# MainBoard_v7_1_3.net
KiCad netlist of a schematic drawn in EAGLE
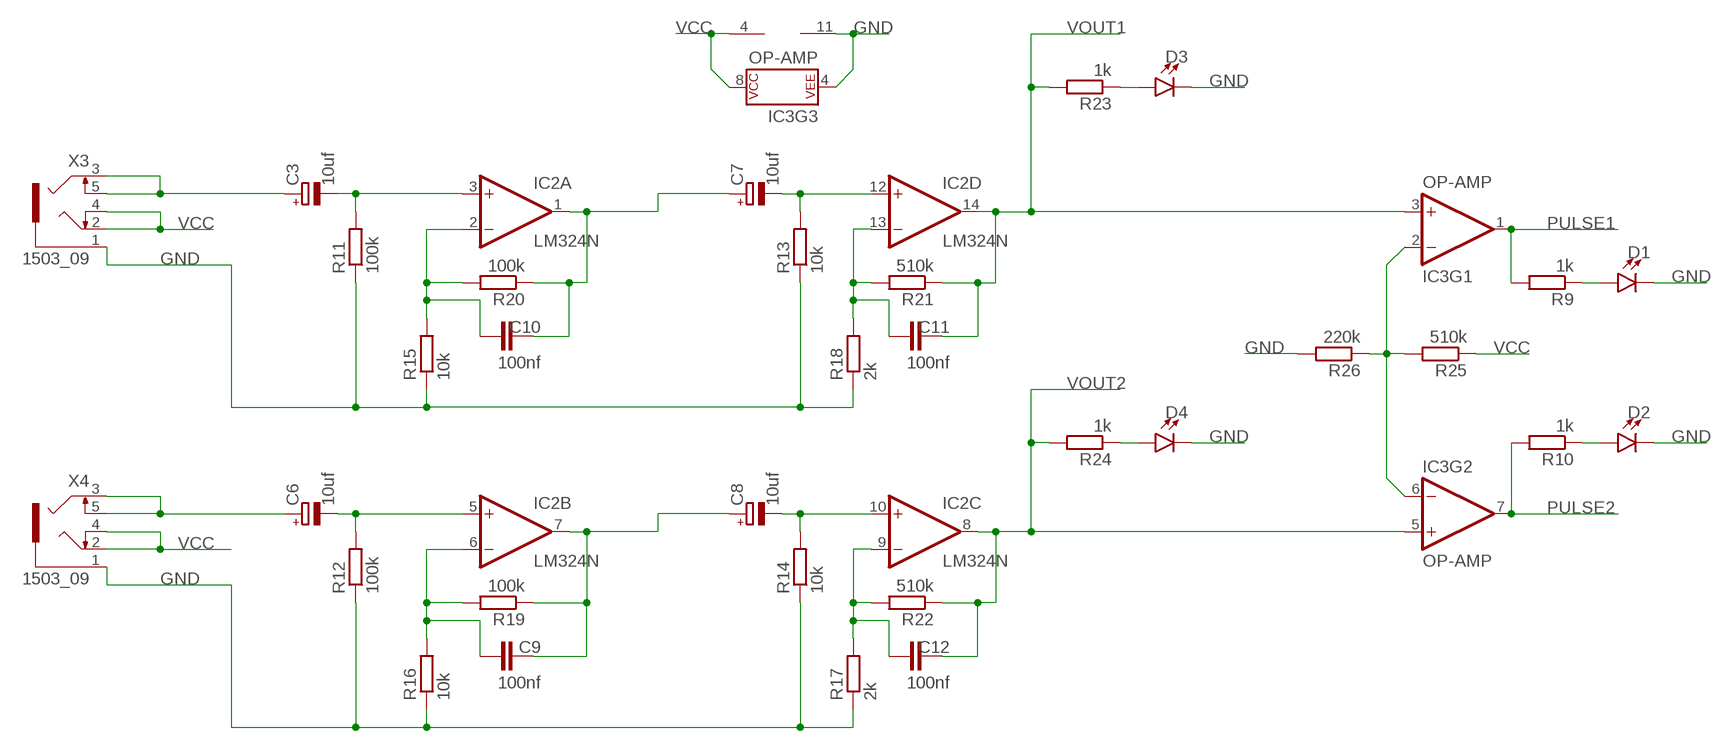
[diagram p0: schematic, sheet 1]
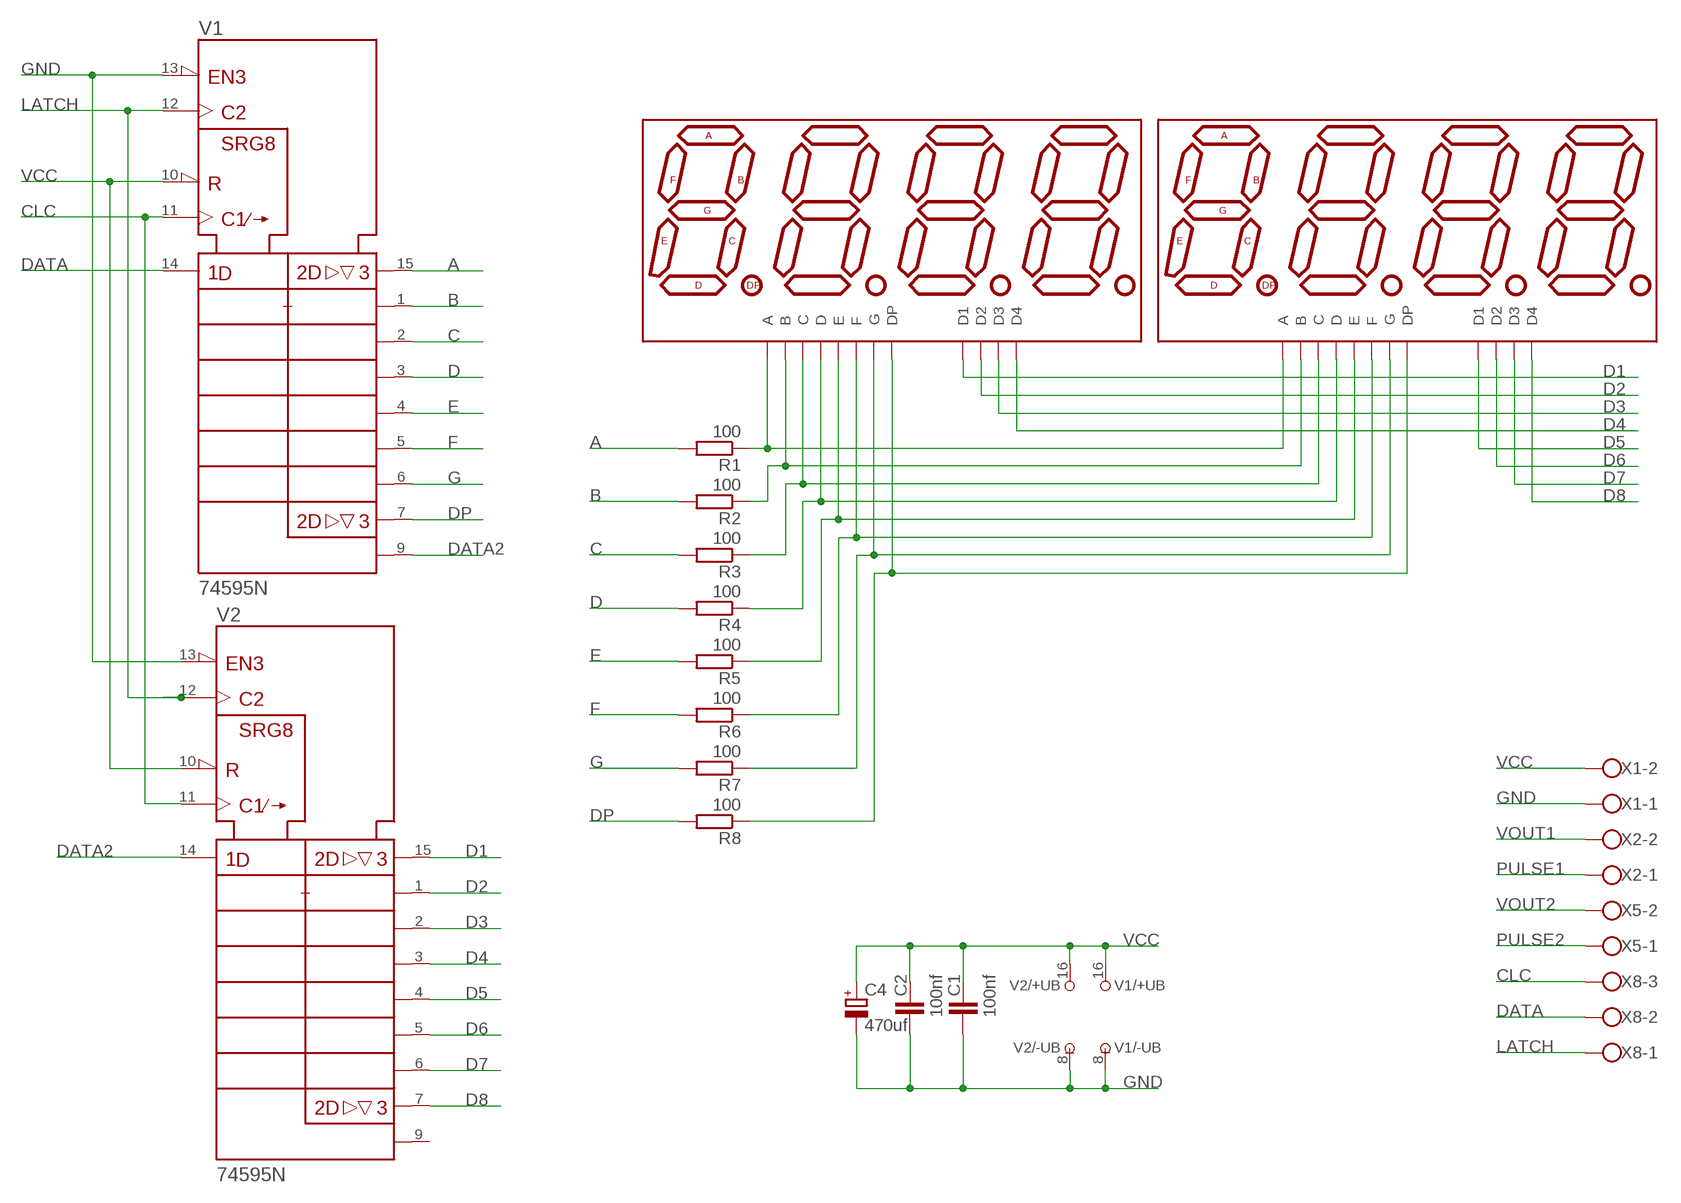
[diagram p1: schematic, sheet 2]

(export (version "E")
  (design (tool "Eeschema 10.0.6"))
  (components
    (comp (ref "C3")
      (value "10uf")
      (footprint "eagle-import:E2-5")
      (libsource (lib "eagle-import") (part "CPOL-EUE2-5"))
    )
    (comp (ref "C6")
      (value "10uf")
      (footprint "eagle-import:E2-5")
      (libsource (lib "eagle-import") (part "CPOL-EUE2-5"))
    )
    (comp (ref "C7")
      (value "10uf")
      (footprint "eagle-import:E2-5")
      (libsource (lib "eagle-import") (part "CPOL-EUE2-5"))
    )
    (comp (ref "C8")
      (value "10uf")
      (footprint "eagle-import:E2-5")
      (libsource (lib "eagle-import") (part "CPOL-EUE2-5"))
    )
    (comp (ref "C9")
      (value "100nf")
      (footprint "eagle-import:C050-030X075")
      (libsource (lib "eagle-import") (part "C-EU050-030X075"))
    )
    (comp (ref "C10")
      (value "100nf")
      (footprint "eagle-import:C050-030X075")
      (libsource (lib "eagle-import") (part "C-EU050-030X075"))
    )
    (comp (ref "C11")
      (value "100nf")
      (footprint "eagle-import:C050-030X075")
      (libsource (lib "eagle-import") (part "C-EU050-030X075"))
    )
    (comp (ref "C12")
      (value "100nf")
      (footprint "eagle-import:C050-030X075")
      (libsource (lib "eagle-import") (part "C-EU050-030X075"))
    )
    (comp (ref "D1")
      (value "LED5MM")
      (footprint "eagle-import:LED_5MM")
      (libsource (lib "eagle-import") (part "LED5MM"))
    )
    (comp (ref "D2")
      (value "LED5MM")
      (footprint "eagle-import:LED_5MM")
      (libsource (lib "eagle-import") (part "LED5MM"))
    )
    (comp (ref "D3")
      (value "LED5MM")
      (footprint "eagle-import:LED_5MM")
      (libsource (lib "eagle-import") (part "LED5MM"))
    )
    (comp (ref "D4")
      (value "LED5MM")
      (footprint "eagle-import:LED_5MM")
      (libsource (lib "eagle-import") (part "LED5MM"))
    )
    (comp (ref "IC2")
      (value "LM324N")
      (footprint "eagle-import:DIL14")
      (libsource (lib "eagle-import") (part "LM324N"))
    )
    (comp (ref "IC3")
      (value "OP-AMP")
      (footprint "eagle-import:DIP08")
      (libsource (lib "eagle-import") (part "OPAMP-DUALDIP"))
    )
    (comp (ref "R9")
      (value "1k")
      (footprint "eagle-import:0207_10")
      (libsource (lib "eagle-import") (part "R-EU_0207/10"))
    )
    (comp (ref "R10")
      (value "1k")
      (footprint "eagle-import:0207_10")
      (libsource (lib "eagle-import") (part "R-EU_0207/10"))
    )
    (comp (ref "R11")
      (value "100k")
      (footprint "eagle-import:0207_10")
      (libsource (lib "eagle-import") (part "R-EU_0207/10"))
    )
    (comp (ref "R12")
      (value "100k")
      (footprint "eagle-import:0207_10")
      (libsource (lib "eagle-import") (part "R-EU_0207/10"))
    )
    (comp (ref "R13")
      (value "10k")
      (footprint "eagle-import:0207_10")
      (libsource (lib "eagle-import") (part "R-EU_0207/10"))
    )
    (comp (ref "R14")
      (value "10k")
      (footprint "eagle-import:0207_10")
      (libsource (lib "eagle-import") (part "R-EU_0207/10"))
    )
    (comp (ref "R15")
      (value "10k")
      (footprint "eagle-import:0207_10")
      (libsource (lib "eagle-import") (part "R-EU_0207/10"))
    )
    (comp (ref "R16")
      (value "10k")
      (footprint "eagle-import:0207_10")
      (libsource (lib "eagle-import") (part "R-EU_0207/10"))
    )
    (comp (ref "R17")
      (value "2k")
      (footprint "eagle-import:0207_10")
      (libsource (lib "eagle-import") (part "R-EU_0207/10"))
    )
    (comp (ref "R18")
      (value "2k")
      (footprint "eagle-import:0207_10")
      (libsource (lib "eagle-import") (part "R-EU_0207/10"))
    )
    (comp (ref "R19")
      (value "100k")
      (footprint "eagle-import:0207_10")
      (libsource (lib "eagle-import") (part "R-EU_0207/10"))
    )
    (comp (ref "R20")
      (value "100k")
      (footprint "eagle-import:0207_10")
      (libsource (lib "eagle-import") (part "R-EU_0207/10"))
    )
    (comp (ref "R21")
      (value "510k")
      (footprint "eagle-import:0207_10")
      (libsource (lib "eagle-import") (part "R-EU_0207/10"))
    )
    (comp (ref "R22")
      (value "510k")
      (footprint "eagle-import:0207_10")
      (libsource (lib "eagle-import") (part "R-EU_0207/10"))
    )
    (comp (ref "R23")
      (value "1k")
      (footprint "eagle-import:0207_10")
      (libsource (lib "eagle-import") (part "R-EU_0207/10"))
    )
    (comp (ref "R24")
      (value "1k")
      (footprint "eagle-import:0207_10")
      (libsource (lib "eagle-import") (part "R-EU_0207/10"))
    )
    (comp (ref "R25")
      (value "510k")
      (footprint "eagle-import:0207_10")
      (libsource (lib "eagle-import") (part "R-EU_0207/10"))
    )
    (comp (ref "R26")
      (value "220k")
      (footprint "eagle-import:0207_10")
      (libsource (lib "eagle-import") (part "R-EU_0207/10"))
    )
    (comp (ref "X3")
      (value "1503_09")
      (footprint "eagle-import:1503_09")
      (libsource (lib "eagle-import") (part "1503_09"))
    )
    (comp (ref "X4")
      (value "1503_09")
      (footprint "eagle-import:1503_09")
      (libsource (lib "eagle-import") (part "1503_09"))
    )
    (comp (ref "C1")
      (value "100nf")
      (footprint "eagle-import:C050-030X075")
      (libsource (lib "eagle-import") (part "C-EU050-030X075"))
    )
    (comp (ref "C2")
      (value "100nf")
      (footprint "eagle-import:C050-030X075")
      (libsource (lib "eagle-import") (part "C-EU050-030X075"))
    )
    (comp (ref "C4")
      (value "470uf")
      (footprint "eagle-import:E3,5-8")
      (libsource (lib "eagle-import") (part "CPOL-EUE3.5-8"))
    )
    (comp (ref "DISP1")
      (value "ATA8041AB")
      (footprint "eagle-import:7-SEGMENT-4DIGIT-20MM")
      (libsource (lib "eagle-import") (part "7-SEGMENT-4DIGIT-20MM-BLUE"))
    )
    (comp (ref "DISP2")
      (value "ATA8041AB")
      (footprint "eagle-import:7-SEGMENT-4DIGIT-20MM")
      (libsource (lib "eagle-import") (part "7-SEGMENT-4DIGIT-20MM-BLUE"))
    )
    (comp (ref "R1")
      (value "100")
      (footprint "eagle-import:0207_10")
      (libsource (lib "eagle-import") (part "R-EU_0207/10"))
    )
    (comp (ref "R2")
      (value "100")
      (footprint "eagle-import:0207_10")
      (libsource (lib "eagle-import") (part "R-EU_0207/10"))
    )
    (comp (ref "R3")
      (value "100")
      (footprint "eagle-import:0207_10")
      (libsource (lib "eagle-import") (part "R-EU_0207/10"))
    )
    (comp (ref "R4")
      (value "100")
      (footprint "eagle-import:0207_10")
      (libsource (lib "eagle-import") (part "R-EU_0207/10"))
    )
    (comp (ref "R5")
      (value "100")
      (footprint "eagle-import:0207_10")
      (libsource (lib "eagle-import") (part "R-EU_0207/10"))
    )
    (comp (ref "R6")
      (value "100")
      (footprint "eagle-import:0207_10")
      (libsource (lib "eagle-import") (part "R-EU_0207/10"))
    )
    (comp (ref "R7")
      (value "100")
      (footprint "eagle-import:0207_10")
      (libsource (lib "eagle-import") (part "R-EU_0207/10"))
    )
    (comp (ref "R8")
      (value "100")
      (footprint "eagle-import:0207_10")
      (libsource (lib "eagle-import") (part "R-EU_0207/10"))
    )
    (comp (ref "V1")
      (value "74595N")
      (footprint "eagle-import:DIL16")
      (libsource (lib "eagle-import") (part "74595N"))
    )
    (comp (ref "V2")
      (value "74595N")
      (footprint "eagle-import:DIL16")
      (libsource (lib "eagle-import") (part "74595N"))
    )
    (comp (ref "X1")
      (value "W237-102")
      (footprint "eagle-import:W237-102")
      (fields (field (name "MPN") "237-102"))
      (libsource (lib "eagle-import") (part "W237-102"))
    )
    (comp (ref "X2")
      (value "W237-102")
      (footprint "eagle-import:W237-102")
      (fields (field (name "MPN") "237-102"))
      (libsource (lib "eagle-import") (part "W237-102"))
    )
    (comp (ref "X5")
      (value "W237-102")
      (footprint "eagle-import:W237-102")
      (fields (field (name "MPN") "237-102"))
      (libsource (lib "eagle-import") (part "W237-102"))
    )
    (comp (ref "X8")
      (value "W237-103")
      (footprint "eagle-import:W237-103")
      (fields (field (name "MPN") "237-103"))
      (libsource (lib "eagle-import") (part "W237-103"))
    )
  )
  (nets
    (net (code "1") (name "A") (class "Default")
      (node (ref "R1") (pin "2") (pinfunction "2_2") (pintype "passive"))
      (node (ref "V1") (pin "15") (pinfunction "QA_15") (pintype "tri_state"))
    )
    (net (code "2") (name "B") (class "Default")
      (node (ref "R2") (pin "2") (pinfunction "2_2") (pintype "passive"))
      (node (ref "V1") (pin "1") (pinfunction "QB_1") (pintype "tri_state"))
    )
    (net (code "3") (name "C") (class "Default")
      (node (ref "R3") (pin "2") (pinfunction "2_2") (pintype "passive"))
      (node (ref "V1") (pin "2") (pinfunction "QC_2") (pintype "tri_state"))
    )
    (net (code "4") (name "CLC") (class "Default")
      (node (ref "V1") (pin "11") (pinfunction "SRCK_11") (pintype "input"))
      (node (ref "V2") (pin "11") (pinfunction "SRCK_11") (pintype "input"))
      (node (ref "X8") (pin "3") (pinfunction "KL_3") (pintype "passive"))
    )
    (net (code "5") (name "D") (class "Default")
      (node (ref "R4") (pin "2") (pinfunction "2_2") (pintype "passive"))
      (node (ref "V1") (pin "3") (pinfunction "QD_3") (pintype "tri_state"))
    )
    (net (code "6") (name "D1") (class "Default")
      (node (ref "DISP2") (pin "12") (pinfunction "D1_12") (pintype "bidirectional"))
      (node (ref "V2") (pin "15") (pinfunction "QA_15") (pintype "tri_state"))
    )
    (net (code "7") (name "D2") (class "Default")
      (node (ref "DISP2") (pin "9") (pinfunction "D2_9") (pintype "bidirectional"))
      (node (ref "V2") (pin "1") (pinfunction "QB_1") (pintype "tri_state"))
    )
    (net (code "8") (name "D3") (class "Default")
      (node (ref "DISP2") (pin "8") (pinfunction "D3_8") (pintype "bidirectional"))
      (node (ref "V2") (pin "2") (pinfunction "QC_2") (pintype "tri_state"))
    )
    (net (code "9") (name "D4") (class "Default")
      (node (ref "DISP2") (pin "6") (pinfunction "D4_6") (pintype "bidirectional"))
      (node (ref "V2") (pin "3") (pinfunction "QD_3") (pintype "tri_state"))
    )
    (net (code "10") (name "D5") (class "Default")
      (node (ref "DISP1") (pin "12") (pinfunction "D1_12") (pintype "bidirectional"))
      (node (ref "V2") (pin "4") (pinfunction "QE_4") (pintype "tri_state"))
    )
    (net (code "11") (name "D6") (class "Default")
      (node (ref "DISP1") (pin "9") (pinfunction "D2_9") (pintype "bidirectional"))
      (node (ref "V2") (pin "5") (pinfunction "QF_5") (pintype "tri_state"))
    )
    (net (code "12") (name "D7") (class "Default")
      (node (ref "DISP1") (pin "8") (pinfunction "D3_8") (pintype "bidirectional"))
      (node (ref "V2") (pin "6") (pinfunction "QG_6") (pintype "tri_state"))
    )
    (net (code "13") (name "D8") (class "Default")
      (node (ref "DISP1") (pin "6") (pinfunction "D4_6") (pintype "bidirectional"))
      (node (ref "V2") (pin "7") (pinfunction "QH_7") (pintype "tri_state"))
    )
    (net (code "14") (name "DATA") (class "Default")
      (node (ref "V1") (pin "14") (pinfunction "SER_14") (pintype "input"))
      (node (ref "X8") (pin "2") (pinfunction "KL_2") (pintype "passive"))
    )
    (net (code "15") (name "DATA2") (class "Default")
      (node (ref "V1") (pin "9") (pinfunction "QH*_9") (pintype "output"))
      (node (ref "V2") (pin "14") (pinfunction "SER_14") (pintype "input"))
    )
    (net (code "16") (name "DP") (class "Default")
      (node (ref "R8") (pin "2") (pinfunction "2_2") (pintype "passive"))
      (node (ref "V1") (pin "7") (pinfunction "QH_7") (pintype "tri_state"))
    )
    (net (code "17") (name "E") (class "Default")
      (node (ref "R5") (pin "2") (pinfunction "2_2") (pintype "passive"))
      (node (ref "V1") (pin "4") (pinfunction "QE_4") (pintype "tri_state"))
    )
    (net (code "18") (name "F") (class "Default")
      (node (ref "R6") (pin "2") (pinfunction "2_2") (pintype "passive"))
      (node (ref "V1") (pin "5") (pinfunction "QF_5") (pintype "tri_state"))
    )
    (net (code "19") (name "G") (class "Default")
      (node (ref "R7") (pin "2") (pinfunction "2_2") (pintype "passive"))
      (node (ref "V1") (pin "6") (pinfunction "QG_6") (pintype "tri_state"))
    )
    (net (code "20") (name "GND") (class "Default")
      (node (ref "C1") (pin "1") (pinfunction "1_1") (pintype "passive"))
      (node (ref "C2") (pin "1") (pinfunction "1_1") (pintype "passive"))
      (node (ref "C4") (pin "-") (pinfunction "-_-") (pintype "passive"))
      (node (ref "D1") (pin "K") (pinfunction "C_K") (pintype "passive"))
      (node (ref "D2") (pin "K") (pinfunction "C_K") (pintype "passive"))
      (node (ref "D3") (pin "K") (pinfunction "C_K") (pintype "passive"))
      (node (ref "D4") (pin "K") (pinfunction "C_K") (pintype "passive"))
      (node (ref "IC2") (pin "11") (pinfunction "V-_11") (pintype "power_in"))
      (node (ref "IC3") (pin "4") (pinfunction "P$V-_4") (pintype "bidirectional"))
      (node (ref "R11") (pin "1") (pinfunction "1_1") (pintype "passive"))
      (node (ref "R12") (pin "1") (pinfunction "1_1") (pintype "passive"))
      (node (ref "R13") (pin "1") (pinfunction "1_1") (pintype "passive"))
      (node (ref "R14") (pin "1") (pinfunction "1_1") (pintype "passive"))
      (node (ref "R15") (pin "1") (pinfunction "1_1") (pintype "passive"))
      (node (ref "R16") (pin "1") (pinfunction "1_1") (pintype "passive"))
      (node (ref "R17") (pin "1") (pinfunction "1_1") (pintype "passive"))
      (node (ref "R18") (pin "1") (pinfunction "1_1") (pintype "passive"))
      (node (ref "R26") (pin "2") (pinfunction "2_2") (pintype "passive"))
      (node (ref "V1") (pin "13") (pinfunction "~{G}_13") (pintype "input"))
      (node (ref "V1") (pin "8") (pinfunction "-UB_8") (pintype "power_in"))
      (node (ref "V2") (pin "13") (pinfunction "~{G}_13") (pintype "input"))
      (node (ref "V2") (pin "8") (pinfunction "-UB_8") (pintype "power_in"))
      (node (ref "X1") (pin "1") (pinfunction "KL_1") (pintype "passive"))
      (node (ref "X3") (pin "1") (pinfunction "1_1") (pintype "passive"))
      (node (ref "X4") (pin "1") (pinfunction "1_1") (pintype "passive"))
    )
    (net (code "21") (name "LATCH") (class "Default")
      (node (ref "V1") (pin "12") (pinfunction "RCK_12") (pintype "input"))
      (node (ref "V2") (pin "12") (pinfunction "RCK_12") (pintype "input"))
      (node (ref "X8") (pin "1") (pinfunction "KL_1") (pintype "passive"))
    )
    (net (code "22") (name "Net-(C3-Pad+)") (class "Default")
      (node (ref "C3") (pin "+") (pinfunction "+_+") (pintype "passive"))
      (node (ref "X3") (pin "3") (pinfunction "3_3") (pintype "passive"))
      (node (ref "X3") (pin "5") (pinfunction "5_5") (pintype "passive"))
    )
    (net (code "23") (name "Net-(C6-Pad+)") (class "Default")
      (node (ref "C6") (pin "+") (pinfunction "+_+") (pintype "passive"))
      (node (ref "X4") (pin "3") (pinfunction "3_3") (pintype "passive"))
      (node (ref "X4") (pin "5") (pinfunction "5_5") (pintype "passive"))
    )
    (net (code "24") (name "Net-(D1-PadA)") (class "Default")
      (node (ref "D1") (pin "A") (pinfunction "A_A") (pintype "passive"))
      (node (ref "R9") (pin "1") (pinfunction "1_1") (pintype "passive"))
    )
    (net (code "25") (name "Net-(D2-PadA)") (class "Default")
      (node (ref "D2") (pin "A") (pinfunction "A_A") (pintype "passive"))
      (node (ref "R10") (pin "1") (pinfunction "1_1") (pintype "passive"))
    )
    (net (code "26") (name "Net-(D3-PadA)") (class "Default")
      (node (ref "D3") (pin "A") (pinfunction "A_A") (pintype "passive"))
      (node (ref "R23") (pin "1") (pinfunction "1_1") (pintype "passive"))
    )
    (net (code "27") (name "Net-(D4-PadA)") (class "Default")
      (node (ref "D4") (pin "A") (pinfunction "A_A") (pintype "passive"))
      (node (ref "R24") (pin "1") (pinfunction "1_1") (pintype "passive"))
    )
    (net (code "28") (name "Net-(DISP1-A)") (class "Default")
      (node (ref "DISP1") (pin "11") (pinfunction "A_11") (pintype "bidirectional"))
      (node (ref "DISP2") (pin "11") (pinfunction "A_11") (pintype "bidirectional"))
      (node (ref "R1") (pin "1") (pinfunction "1_1") (pintype "passive"))
    )
    (net (code "29") (name "Net-(DISP1-B)") (class "Default")
      (node (ref "DISP1") (pin "7") (pinfunction "B_7") (pintype "bidirectional"))
      (node (ref "DISP2") (pin "7") (pinfunction "B_7") (pintype "bidirectional"))
      (node (ref "R2") (pin "1") (pinfunction "1_1") (pintype "passive"))
    )
    (net (code "30") (name "Net-(DISP1-C)") (class "Default")
      (node (ref "DISP1") (pin "4") (pinfunction "C_4") (pintype "bidirectional"))
      (node (ref "DISP2") (pin "4") (pinfunction "C_4") (pintype "bidirectional"))
      (node (ref "R3") (pin "1") (pinfunction "1_1") (pintype "passive"))
    )
    (net (code "31") (name "Net-(DISP1-D)") (class "Default")
      (node (ref "DISP1") (pin "2") (pinfunction "D_2") (pintype "bidirectional"))
      (node (ref "DISP2") (pin "2") (pinfunction "D_2") (pintype "bidirectional"))
      (node (ref "R4") (pin "1") (pinfunction "1_1") (pintype "passive"))
    )
    (net (code "32") (name "Net-(DISP1-DP)") (class "Default")
      (node (ref "DISP1") (pin "3") (pinfunction "DP_3") (pintype "bidirectional"))
      (node (ref "DISP2") (pin "3") (pinfunction "DP_3") (pintype "bidirectional"))
      (node (ref "R8") (pin "1") (pinfunction "1_1") (pintype "passive"))
    )
    (net (code "33") (name "Net-(DISP1-E)") (class "Default")
      (node (ref "DISP1") (pin "1") (pinfunction "E_1") (pintype "bidirectional"))
      (node (ref "DISP2") (pin "1") (pinfunction "E_1") (pintype "bidirectional"))
      (node (ref "R5") (pin "1") (pinfunction "1_1") (pintype "passive"))
    )
    (net (code "34") (name "Net-(DISP1-F)") (class "Default")
      (node (ref "DISP1") (pin "10") (pinfunction "F_10") (pintype "bidirectional"))
      (node (ref "DISP2") (pin "10") (pinfunction "F_10") (pintype "bidirectional"))
      (node (ref "R6") (pin "1") (pinfunction "1_1") (pintype "passive"))
    )
    (net (code "35") (name "Net-(DISP1-G)") (class "Default")
      (node (ref "DISP1") (pin "5") (pinfunction "G_5") (pintype "bidirectional"))
      (node (ref "DISP2") (pin "5") (pinfunction "G_5") (pintype "bidirectional"))
      (node (ref "R7") (pin "1") (pinfunction "1_1") (pintype "passive"))
    )
    (net (code "36") (name "Net-(IC2A-+IN)") (class "Default")
      (node (ref "C3") (pin "-") (pinfunction "-_-") (pintype "passive"))
      (node (ref "IC2") (pin "3") (pinfunction "+IN_3") (pintype "input"))
      (node (ref "R11") (pin "2") (pinfunction "2_2") (pintype "passive"))
    )
    (net (code "37") (name "Net-(IC2A--IN)") (class "Default")
      (node (ref "C10") (pin "1") (pinfunction "1_1") (pintype "passive"))
      (node (ref "IC2") (pin "2") (pinfunction "-IN_2") (pintype "input"))
      (node (ref "R15") (pin "2") (pinfunction "2_2") (pintype "passive"))
      (node (ref "R20") (pin "2") (pinfunction "2_2") (pintype "passive"))
    )
    (net (code "38") (name "Net-(IC2A-OUT)") (class "Default")
      (node (ref "C10") (pin "2") (pinfunction "2_2") (pintype "passive"))
      (node (ref "C7") (pin "+") (pinfunction "+_+") (pintype "passive"))
      (node (ref "IC2") (pin "1") (pinfunction "OUT_1") (pintype "output"))
      (node (ref "R20") (pin "1") (pinfunction "1_1") (pintype "passive"))
    )
    (net (code "39") (name "Net-(IC2B-+IN)") (class "Default")
      (node (ref "C6") (pin "-") (pinfunction "-_-") (pintype "passive"))
      (node (ref "IC2") (pin "5") (pinfunction "+IN_5") (pintype "input"))
      (node (ref "R12") (pin "2") (pinfunction "2_2") (pintype "passive"))
    )
    (net (code "40") (name "Net-(IC2B--IN)") (class "Default")
      (node (ref "C9") (pin "1") (pinfunction "1_1") (pintype "passive"))
      (node (ref "IC2") (pin "6") (pinfunction "-IN_6") (pintype "input"))
      (node (ref "R16") (pin "2") (pinfunction "2_2") (pintype "passive"))
      (node (ref "R19") (pin "2") (pinfunction "2_2") (pintype "passive"))
    )
    (net (code "41") (name "Net-(IC2B-OUT)") (class "Default")
      (node (ref "C8") (pin "+") (pinfunction "+_+") (pintype "passive"))
      (node (ref "C9") (pin "2") (pinfunction "2_2") (pintype "passive"))
      (node (ref "IC2") (pin "7") (pinfunction "OUT_7") (pintype "output"))
      (node (ref "R19") (pin "1") (pinfunction "1_1") (pintype "passive"))
    )
    (net (code "42") (name "Net-(IC2C-+IN)") (class "Default")
      (node (ref "C8") (pin "-") (pinfunction "-_-") (pintype "passive"))
      (node (ref "IC2") (pin "10") (pinfunction "+IN_10") (pintype "input"))
      (node (ref "R14") (pin "2") (pinfunction "2_2") (pintype "passive"))
    )
    (net (code "43") (name "Net-(IC2C--IN)") (class "Default")
      (node (ref "C12") (pin "1") (pinfunction "1_1") (pintype "passive"))
      (node (ref "IC2") (pin "9") (pinfunction "-IN_9") (pintype "input"))
      (node (ref "R17") (pin "2") (pinfunction "2_2") (pintype "passive"))
      (node (ref "R22") (pin "2") (pinfunction "2_2") (pintype "passive"))
    )
    (net (code "44") (name "Net-(IC2D-+IN)") (class "Default")
      (node (ref "C7") (pin "-") (pinfunction "-_-") (pintype "passive"))
      (node (ref "IC2") (pin "12") (pinfunction "+IN_12") (pintype "input"))
      (node (ref "R13") (pin "2") (pinfunction "2_2") (pintype "passive"))
    )
    (net (code "45") (name "Net-(IC2D--IN)") (class "Default")
      (node (ref "C11") (pin "1") (pinfunction "1_1") (pintype "passive"))
      (node (ref "IC2") (pin "13") (pinfunction "-IN_13") (pintype "input"))
      (node (ref "R18") (pin "2") (pinfunction "2_2") (pintype "passive"))
      (node (ref "R21") (pin "2") (pinfunction "2_2") (pintype "passive"))
    )
    (net (code "46") (name "Net-(IC3A--IN)") (class "Default")
      (node (ref "IC3") (pin "2") (pinfunction "-IN_2") (pintype "input"))
      (node (ref "IC3") (pin "6") (pinfunction "-IN_6") (pintype "input"))
      (node (ref "R25") (pin "2") (pinfunction "2_2") (pintype "passive"))
      (node (ref "R26") (pin "1") (pinfunction "1_1") (pintype "passive"))
    )
    (net (code "47") (name "PULSE1") (class "Default")
      (node (ref "IC3") (pin "1") (pinfunction "OUT_1") (pintype "output"))
      (node (ref "R9") (pin "2") (pinfunction "2_2") (pintype "passive"))
      (node (ref "X2") (pin "1") (pinfunction "KL_1") (pintype "passive"))
    )
    (net (code "48") (name "PULSE2") (class "Default")
      (node (ref "IC3") (pin "7") (pinfunction "OUT_7") (pintype "output"))
      (node (ref "R10") (pin "2") (pinfunction "2_2") (pintype "passive"))
      (node (ref "X5") (pin "1") (pinfunction "KL_1") (pintype "passive"))
    )
    (net (code "49") (name "VCC") (class "Default")
      (node (ref "C1") (pin "2") (pinfunction "2_2") (pintype "passive"))
      (node (ref "C2") (pin "2") (pinfunction "2_2") (pintype "passive"))
      (node (ref "C4") (pin "+") (pinfunction "+_+") (pintype "passive"))
      (node (ref "IC2") (pin "4") (pinfunction "V+_4") (pintype "power_in"))
      (node (ref "IC3") (pin "8") (pinfunction "P$V+_8") (pintype "bidirectional"))
      (node (ref "R25") (pin "1") (pinfunction "1_1") (pintype "passive"))
      (node (ref "V1") (pin "10") (pinfunction "~{SRCLR}_10") (pintype "input"))
      (node (ref "V1") (pin "16") (pinfunction "+UB_16") (pintype "power_in"))
      (node (ref "V2") (pin "10") (pinfunction "~{SRCLR}_10") (pintype "input"))
      (node (ref "V2") (pin "16") (pinfunction "+UB_16") (pintype "power_in"))
      (node (ref "X1") (pin "2") (pinfunction "KL_2") (pintype "passive"))
      (node (ref "X3") (pin "2") (pinfunction "2_2") (pintype "passive"))
      (node (ref "X3") (pin "4") (pinfunction "4_4") (pintype "passive"))
      (node (ref "X4") (pin "2") (pinfunction "2_2") (pintype "passive"))
      (node (ref "X4") (pin "4") (pinfunction "4_4") (pintype "passive"))
    )
    (net (code "50") (name "VOUT1") (class "Default")
      (node (ref "C11") (pin "2") (pinfunction "2_2") (pintype "passive"))
      (node (ref "IC2") (pin "14") (pinfunction "OUT_14") (pintype "output"))
      (node (ref "IC3") (pin "3") (pinfunction "+IN_3") (pintype "input"))
      (node (ref "R21") (pin "1") (pinfunction "1_1") (pintype "passive"))
      (node (ref "R23") (pin "2") (pinfunction "2_2") (pintype "passive"))
      (node (ref "X2") (pin "2") (pinfunction "KL_2") (pintype "passive"))
    )
    (net (code "51") (name "VOUT2") (class "Default")
      (node (ref "C12") (pin "2") (pinfunction "2_2") (pintype "passive"))
      (node (ref "IC2") (pin "8") (pinfunction "OUT_8") (pintype "output"))
      (node (ref "IC3") (pin "5") (pinfunction "+IN_5") (pintype "input"))
      (node (ref "R22") (pin "1") (pinfunction "1_1") (pintype "passive"))
      (node (ref "R24") (pin "2") (pinfunction "2_2") (pintype "passive"))
      (node (ref "X5") (pin "2") (pinfunction "KL_2") (pintype "passive"))
    )
    (net (code "52") (name "unconnected-(V2C-QH*-Pad9)") (class "Default")
      (node (ref "V2") (pin "9") (pinfunction "QH*_9") (pintype "output"))
    )
  )
)
